# eCog119_7Segment.net
KiCad netlist of a schematic drawn in EAGLE
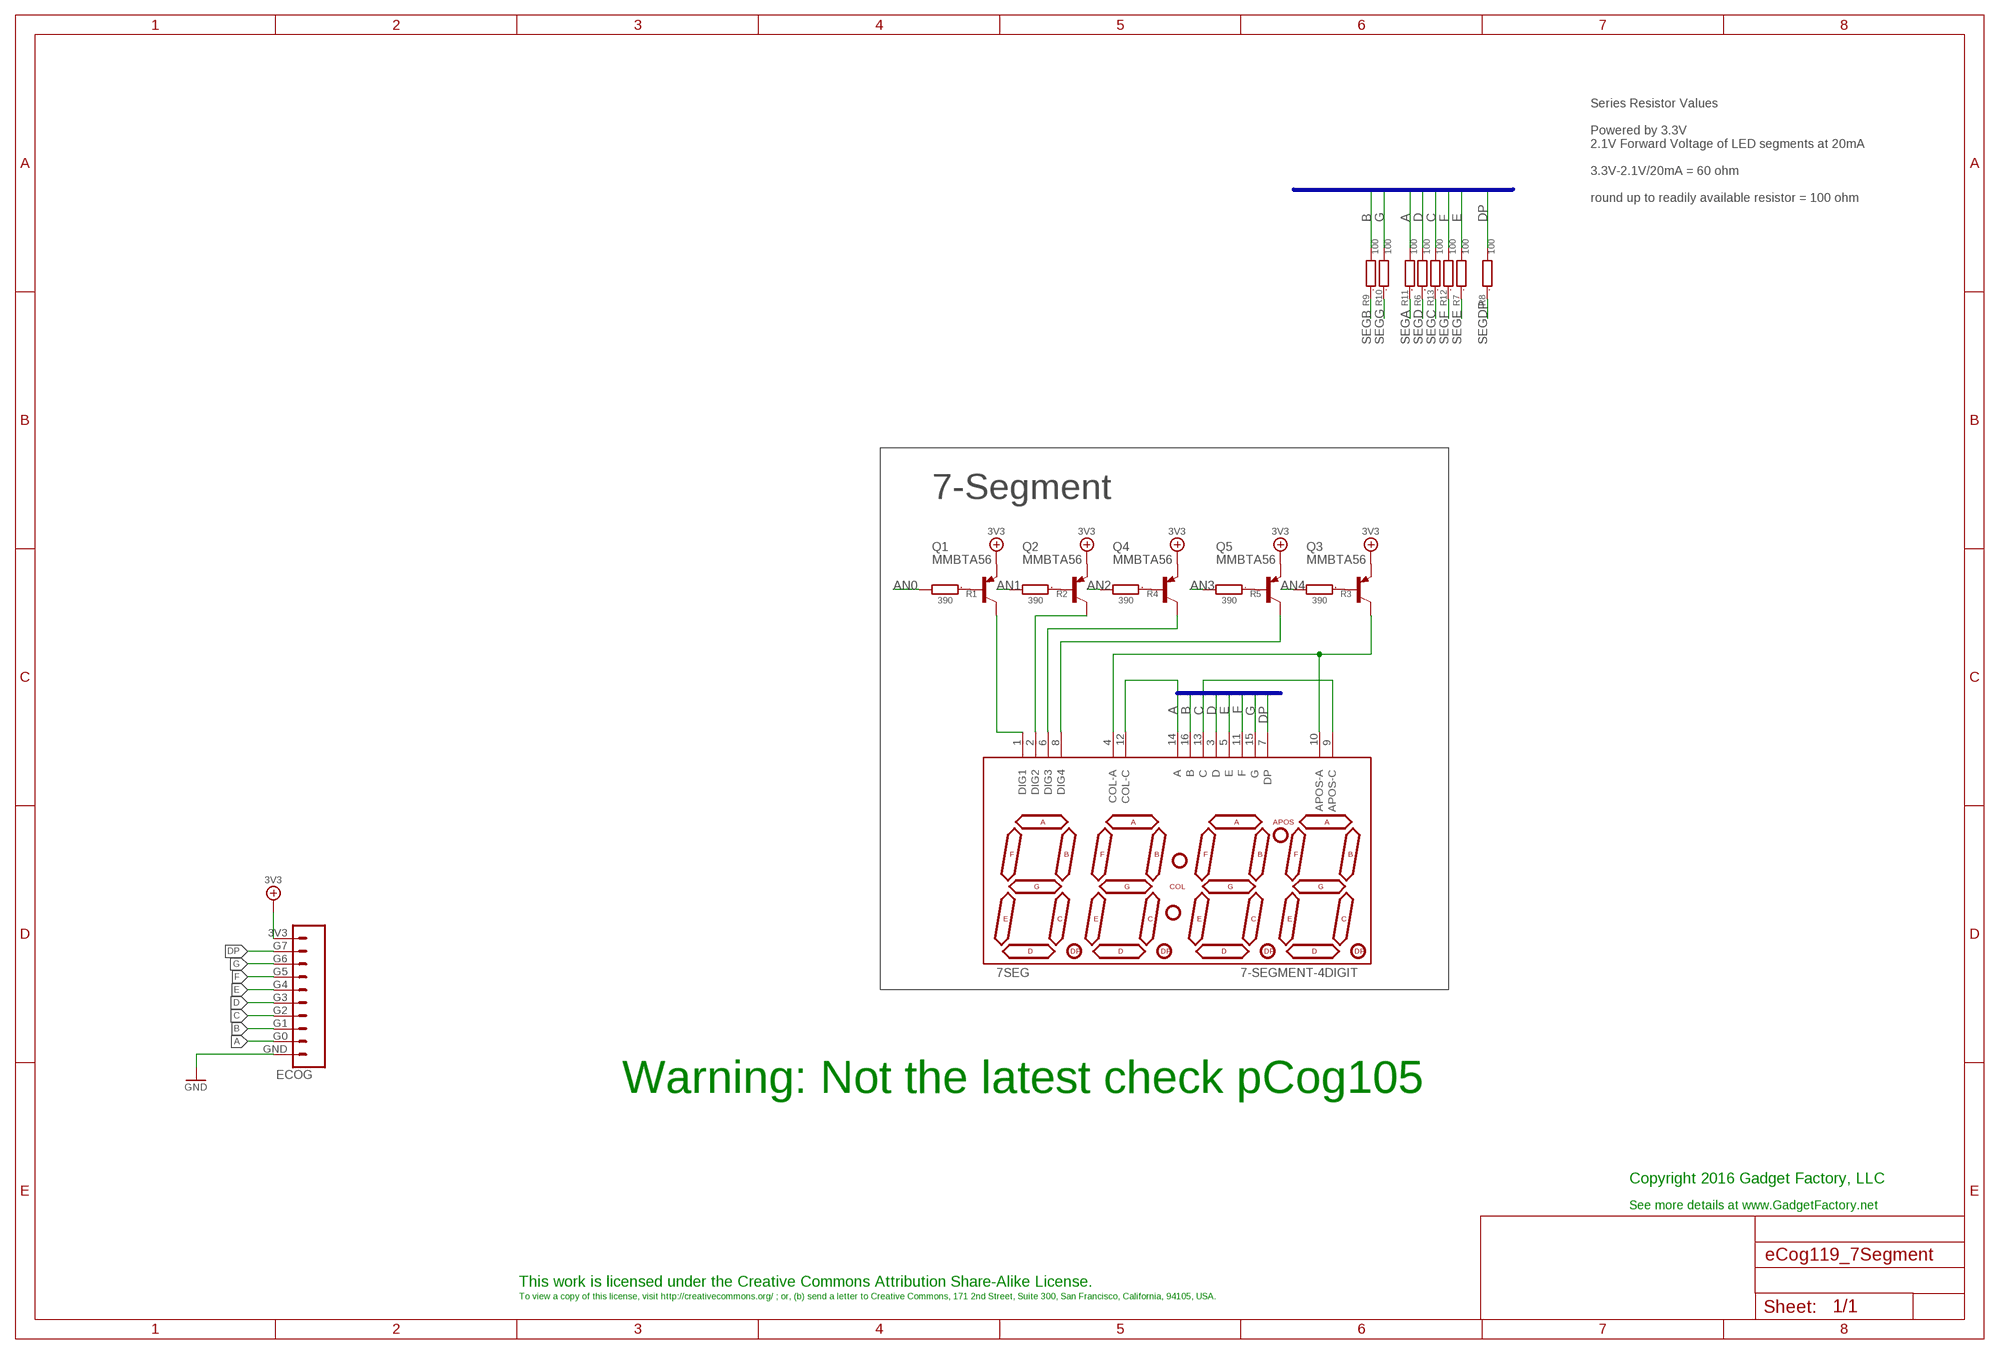
[diagram p0: schematic, sheet 1]

(export (version "E")
  (design (tool "Eeschema 10.0.6"))
  (components
    (comp (ref "7SEG")
      (value "7-SEGMENT-4DIGIT")
      (footprint "eagle-import:7-SEGMENT-4DIGIT")
      (fields (field (name "PARTNO") "AL-D4012BWSR/58-040C"))
      (libsource (lib "eagle-import") (part "7-SEGMENT-4DIGIT"))
    )
    (comp (ref "ECOG")
      (value "ECOG_GENERAL_ROWTHROUGHOLE")
      (footprint "eagle-import:ECOG_GENERAL_TH")
      (libsource (lib "eagle-import") (part "ECOG_GENERAL_ROWTHROUGHOLE"))
    )
    (comp (ref "Q1")
      (value "MMBTA56")
      (footprint "eagle-import:SOT23")
      (libsource (lib "eagle-import") (part "-?SOT23MMBTA56"))
    )
    (comp (ref "Q2")
      (value "MMBTA56")
      (footprint "eagle-import:SOT23")
      (libsource (lib "eagle-import") (part "-?SOT23MMBTA56"))
    )
    (comp (ref "Q3")
      (value "MMBTA56")
      (footprint "eagle-import:SOT23")
      (libsource (lib "eagle-import") (part "-?SOT23MMBTA56"))
    )
    (comp (ref "Q4")
      (value "MMBTA56")
      (footprint "eagle-import:SOT23")
      (libsource (lib "eagle-import") (part "-?SOT23MMBTA56"))
    )
    (comp (ref "Q5")
      (value "MMBTA56")
      (footprint "eagle-import:SOT23")
      (libsource (lib "eagle-import") (part "-?SOT23MMBTA56"))
    )
    (comp (ref "R1")
      (value "390")
      (footprint "eagle-import:0603")
      (fields (field (name "PARTNO") "CRCW0603100RJNEA"))
      (libsource (lib "eagle-import") (part "R0603"))
    )
    (comp (ref "R2")
      (value "390")
      (footprint "eagle-import:0603")
      (fields (field (name "PARTNO") "CRCW0603100RJNEA"))
      (libsource (lib "eagle-import") (part "R0603"))
    )
    (comp (ref "R3")
      (value "390")
      (footprint "eagle-import:0603")
      (fields (field (name "PARTNO") "CRCW0603100RJNEA"))
      (libsource (lib "eagle-import") (part "R0603"))
    )
    (comp (ref "R4")
      (value "390")
      (footprint "eagle-import:0603")
      (fields (field (name "PARTNO") "CRCW0603100RJNEA"))
      (libsource (lib "eagle-import") (part "R0603"))
    )
    (comp (ref "R5")
      (value "390")
      (footprint "eagle-import:0603")
      (fields (field (name "PARTNO") "CRCW0603100RJNEA"))
      (libsource (lib "eagle-import") (part "R0603"))
    )
    (comp (ref "R6")
      (value "100")
      (footprint "eagle-import:0603")
      (fields (field (name "PARTNO") "CRCW0603100RJNEA"))
      (libsource (lib "eagle-import") (part "R0603"))
    )
    (comp (ref "R7")
      (value "100")
      (footprint "eagle-import:0603")
      (fields (field (name "PARTNO") "CRCW0603100RJNEA"))
      (libsource (lib "eagle-import") (part "R0603"))
    )
    (comp (ref "R8")
      (value "100")
      (footprint "eagle-import:0603")
      (fields (field (name "PARTNO") "CRCW0603100RJNEA"))
      (libsource (lib "eagle-import") (part "R0603"))
    )
    (comp (ref "R9")
      (value "100")
      (footprint "eagle-import:0603")
      (fields (field (name "PARTNO") "CRCW0603100RJNEA"))
      (libsource (lib "eagle-import") (part "R0603"))
    )
    (comp (ref "R10")
      (value "100")
      (footprint "eagle-import:0603")
      (fields (field (name "PARTNO") "CRCW0603100RJNEA"))
      (libsource (lib "eagle-import") (part "R0603"))
    )
    (comp (ref "R11")
      (value "100")
      (footprint "eagle-import:0603")
      (fields (field (name "PARTNO") "CRCW0603100RJNEA"))
      (libsource (lib "eagle-import") (part "R0603"))
    )
    (comp (ref "R12")
      (value "100")
      (footprint "eagle-import:0603")
      (fields (field (name "PARTNO") "CRCW0603100RJNEA"))
      (libsource (lib "eagle-import") (part "R0603"))
    )
    (comp (ref "R13")
      (value "100")
      (footprint "eagle-import:0603")
      (fields (field (name "PARTNO") "CRCW0603100RJNEA"))
      (libsource (lib "eagle-import") (part "R0603"))
    )
  )
  (nets
    (net (code "1") (name "/AN0") (class "Default")
      (node (ref "R1") (pin "2") (pinfunction "2_2") (pintype "passive"))
    )
    (net (code "2") (name "/AN1") (class "Default")
      (node (ref "R2") (pin "2") (pinfunction "2_2") (pintype "passive"))
    )
    (net (code "3") (name "/AN2") (class "Default")
      (node (ref "R4") (pin "2") (pinfunction "2_2") (pintype "passive"))
    )
    (net (code "4") (name "/AN3") (class "Default")
      (node (ref "R5") (pin "2") (pinfunction "2_2") (pintype "passive"))
    )
    (net (code "5") (name "/AN4") (class "Default")
      (node (ref "R3") (pin "2") (pinfunction "2_2") (pintype "passive"))
    )
    (net (code "6") (name "/SEGA") (class "Default")
      (node (ref "R11") (pin "1") (pinfunction "1_1") (pintype "passive"))
    )
    (net (code "7") (name "/SEGB") (class "Default")
      (node (ref "R9") (pin "1") (pinfunction "1_1") (pintype "passive"))
    )
    (net (code "8") (name "/SEGC") (class "Default")
      (node (ref "R13") (pin "1") (pinfunction "1_1") (pintype "passive"))
    )
    (net (code "9") (name "/SEGD") (class "Default")
      (node (ref "R6") (pin "1") (pinfunction "1_1") (pintype "passive"))
    )
    (net (code "10") (name "/SEGDP") (class "Default")
      (node (ref "R8") (pin "1") (pinfunction "1_1") (pintype "passive"))
    )
    (net (code "11") (name "/SEGE") (class "Default")
      (node (ref "R7") (pin "1") (pinfunction "1_1") (pintype "passive"))
    )
    (net (code "12") (name "/SEGF") (class "Default")
      (node (ref "R12") (pin "1") (pinfunction "1_1") (pintype "passive"))
    )
    (net (code "13") (name "/SEGG") (class "Default")
      (node (ref "R10") (pin "1") (pinfunction "1_1") (pintype "passive"))
    )
    (net (code "14") (name "3V3") (class "Default")
      (node (ref "ECOG") (pin "3V3") (pinfunction "3V3_3V3") (pintype "power_in"))
      (node (ref "Q1") (pin "2") (pinfunction "E_2") (pintype "passive"))
      (node (ref "Q2") (pin "2") (pinfunction "E_2") (pintype "passive"))
      (node (ref "Q3") (pin "2") (pinfunction "E_2") (pintype "passive"))
      (node (ref "Q4") (pin "2") (pinfunction "E_2") (pintype "passive"))
      (node (ref "Q5") (pin "2") (pinfunction "E_2") (pintype "passive"))
    )
    (net (code "15") (name "A") (class "Default")
      (node (ref "7SEG") (pin "12") (pinfunction "COL-C_12") (pintype "bidirectional"))
      (node (ref "7SEG") (pin "14") (pinfunction "A_14") (pintype "bidirectional"))
      (node (ref "ECOG") (pin "G0") (pinfunction "G0_G0") (pintype "passive"))
      (node (ref "R11") (pin "2") (pinfunction "2_2") (pintype "passive"))
    )
    (net (code "16") (name "B") (class "Default")
      (node (ref "7SEG") (pin "16") (pinfunction "B_16") (pintype "bidirectional"))
      (node (ref "ECOG") (pin "G1") (pinfunction "G1_G1") (pintype "passive"))
      (node (ref "R9") (pin "2") (pinfunction "2_2") (pintype "passive"))
    )
    (net (code "17") (name "C") (class "Default")
      (node (ref "7SEG") (pin "13") (pinfunction "C_13") (pintype "bidirectional"))
      (node (ref "7SEG") (pin "9") (pinfunction "APOS-C_9") (pintype "bidirectional"))
      (node (ref "ECOG") (pin "G2") (pinfunction "G2_G2") (pintype "passive"))
      (node (ref "R13") (pin "2") (pinfunction "2_2") (pintype "passive"))
    )
    (net (code "18") (name "D") (class "Default")
      (node (ref "7SEG") (pin "3") (pinfunction "D_3") (pintype "bidirectional"))
      (node (ref "ECOG") (pin "G3") (pinfunction "G3_G3") (pintype "passive"))
      (node (ref "R6") (pin "2") (pinfunction "2_2") (pintype "passive"))
    )
    (net (code "19") (name "DP") (class "Default")
      (node (ref "7SEG") (pin "7") (pinfunction "DP_7") (pintype "bidirectional"))
      (node (ref "ECOG") (pin "G7") (pinfunction "G7_G7") (pintype "passive"))
      (node (ref "R8") (pin "2") (pinfunction "2_2") (pintype "passive"))
    )
    (net (code "20") (name "E") (class "Default")
      (node (ref "7SEG") (pin "5") (pinfunction "E_5") (pintype "bidirectional"))
      (node (ref "ECOG") (pin "G4") (pinfunction "G4_G4") (pintype "passive"))
      (node (ref "R7") (pin "2") (pinfunction "2_2") (pintype "passive"))
    )
    (net (code "21") (name "F") (class "Default")
      (node (ref "7SEG") (pin "11") (pinfunction "F_11") (pintype "bidirectional"))
      (node (ref "ECOG") (pin "G5") (pinfunction "G5_G5") (pintype "passive"))
      (node (ref "R12") (pin "2") (pinfunction "2_2") (pintype "passive"))
    )
    (net (code "22") (name "G") (class "Default")
      (node (ref "7SEG") (pin "15") (pinfunction "G_15") (pintype "bidirectional"))
      (node (ref "ECOG") (pin "G6") (pinfunction "G6_G6") (pintype "passive"))
      (node (ref "R10") (pin "2") (pinfunction "2_2") (pintype "passive"))
    )
    (net (code "23") (name "GND") (class "Default")
      (node (ref "ECOG") (pin "GND") (pinfunction "GND_GND") (pintype "power_in"))
    )
    (net (code "24") (name "Net-(7SEG-APOS-A)") (class "Default")
      (node (ref "7SEG") (pin "10") (pinfunction "APOS-A_10") (pintype "bidirectional"))
      (node (ref "7SEG") (pin "4") (pinfunction "COL-A_4") (pintype "bidirectional"))
      (node (ref "Q3") (pin "3") (pinfunction "C_3") (pintype "passive"))
    )
    (net (code "25") (name "Net-(7SEG-DIG1)") (class "Default")
      (node (ref "7SEG") (pin "1") (pinfunction "DIG1_1") (pintype "bidirectional"))
      (node (ref "Q1") (pin "3") (pinfunction "C_3") (pintype "passive"))
    )
    (net (code "26") (name "Net-(7SEG-DIG2)") (class "Default")
      (node (ref "7SEG") (pin "2") (pinfunction "DIG2_2") (pintype "bidirectional"))
      (node (ref "Q2") (pin "3") (pinfunction "C_3") (pintype "passive"))
    )
    (net (code "27") (name "Net-(7SEG-DIG3)") (class "Default")
      (node (ref "7SEG") (pin "6") (pinfunction "DIG3_6") (pintype "bidirectional"))
      (node (ref "Q4") (pin "3") (pinfunction "C_3") (pintype "passive"))
    )
    (net (code "28") (name "Net-(7SEG-DIG4)") (class "Default")
      (node (ref "7SEG") (pin "8") (pinfunction "DIG4_8") (pintype "bidirectional"))
      (node (ref "Q5") (pin "3") (pinfunction "C_3") (pintype "passive"))
    )
    (net (code "29") (name "Net-(Q1-B)") (class "Default")
      (node (ref "Q1") (pin "1") (pinfunction "B_1") (pintype "passive"))
      (node (ref "R1") (pin "1") (pinfunction "1_1") (pintype "passive"))
    )
    (net (code "30") (name "Net-(Q2-B)") (class "Default")
      (node (ref "Q2") (pin "1") (pinfunction "B_1") (pintype "passive"))
      (node (ref "R2") (pin "1") (pinfunction "1_1") (pintype "passive"))
    )
    (net (code "31") (name "Net-(Q3-B)") (class "Default")
      (node (ref "Q3") (pin "1") (pinfunction "B_1") (pintype "passive"))
      (node (ref "R3") (pin "1") (pinfunction "1_1") (pintype "passive"))
    )
    (net (code "32") (name "Net-(Q4-B)") (class "Default")
      (node (ref "Q4") (pin "1") (pinfunction "B_1") (pintype "passive"))
      (node (ref "R4") (pin "1") (pinfunction "1_1") (pintype "passive"))
    )
    (net (code "33") (name "Net-(Q5-B)") (class "Default")
      (node (ref "Q5") (pin "1") (pinfunction "B_1") (pintype "passive"))
      (node (ref "R5") (pin "1") (pinfunction "1_1") (pintype "passive"))
    )
  )
)
